# Sheet1.net
KiCad netlist of a schematic drawn in Altium Designer
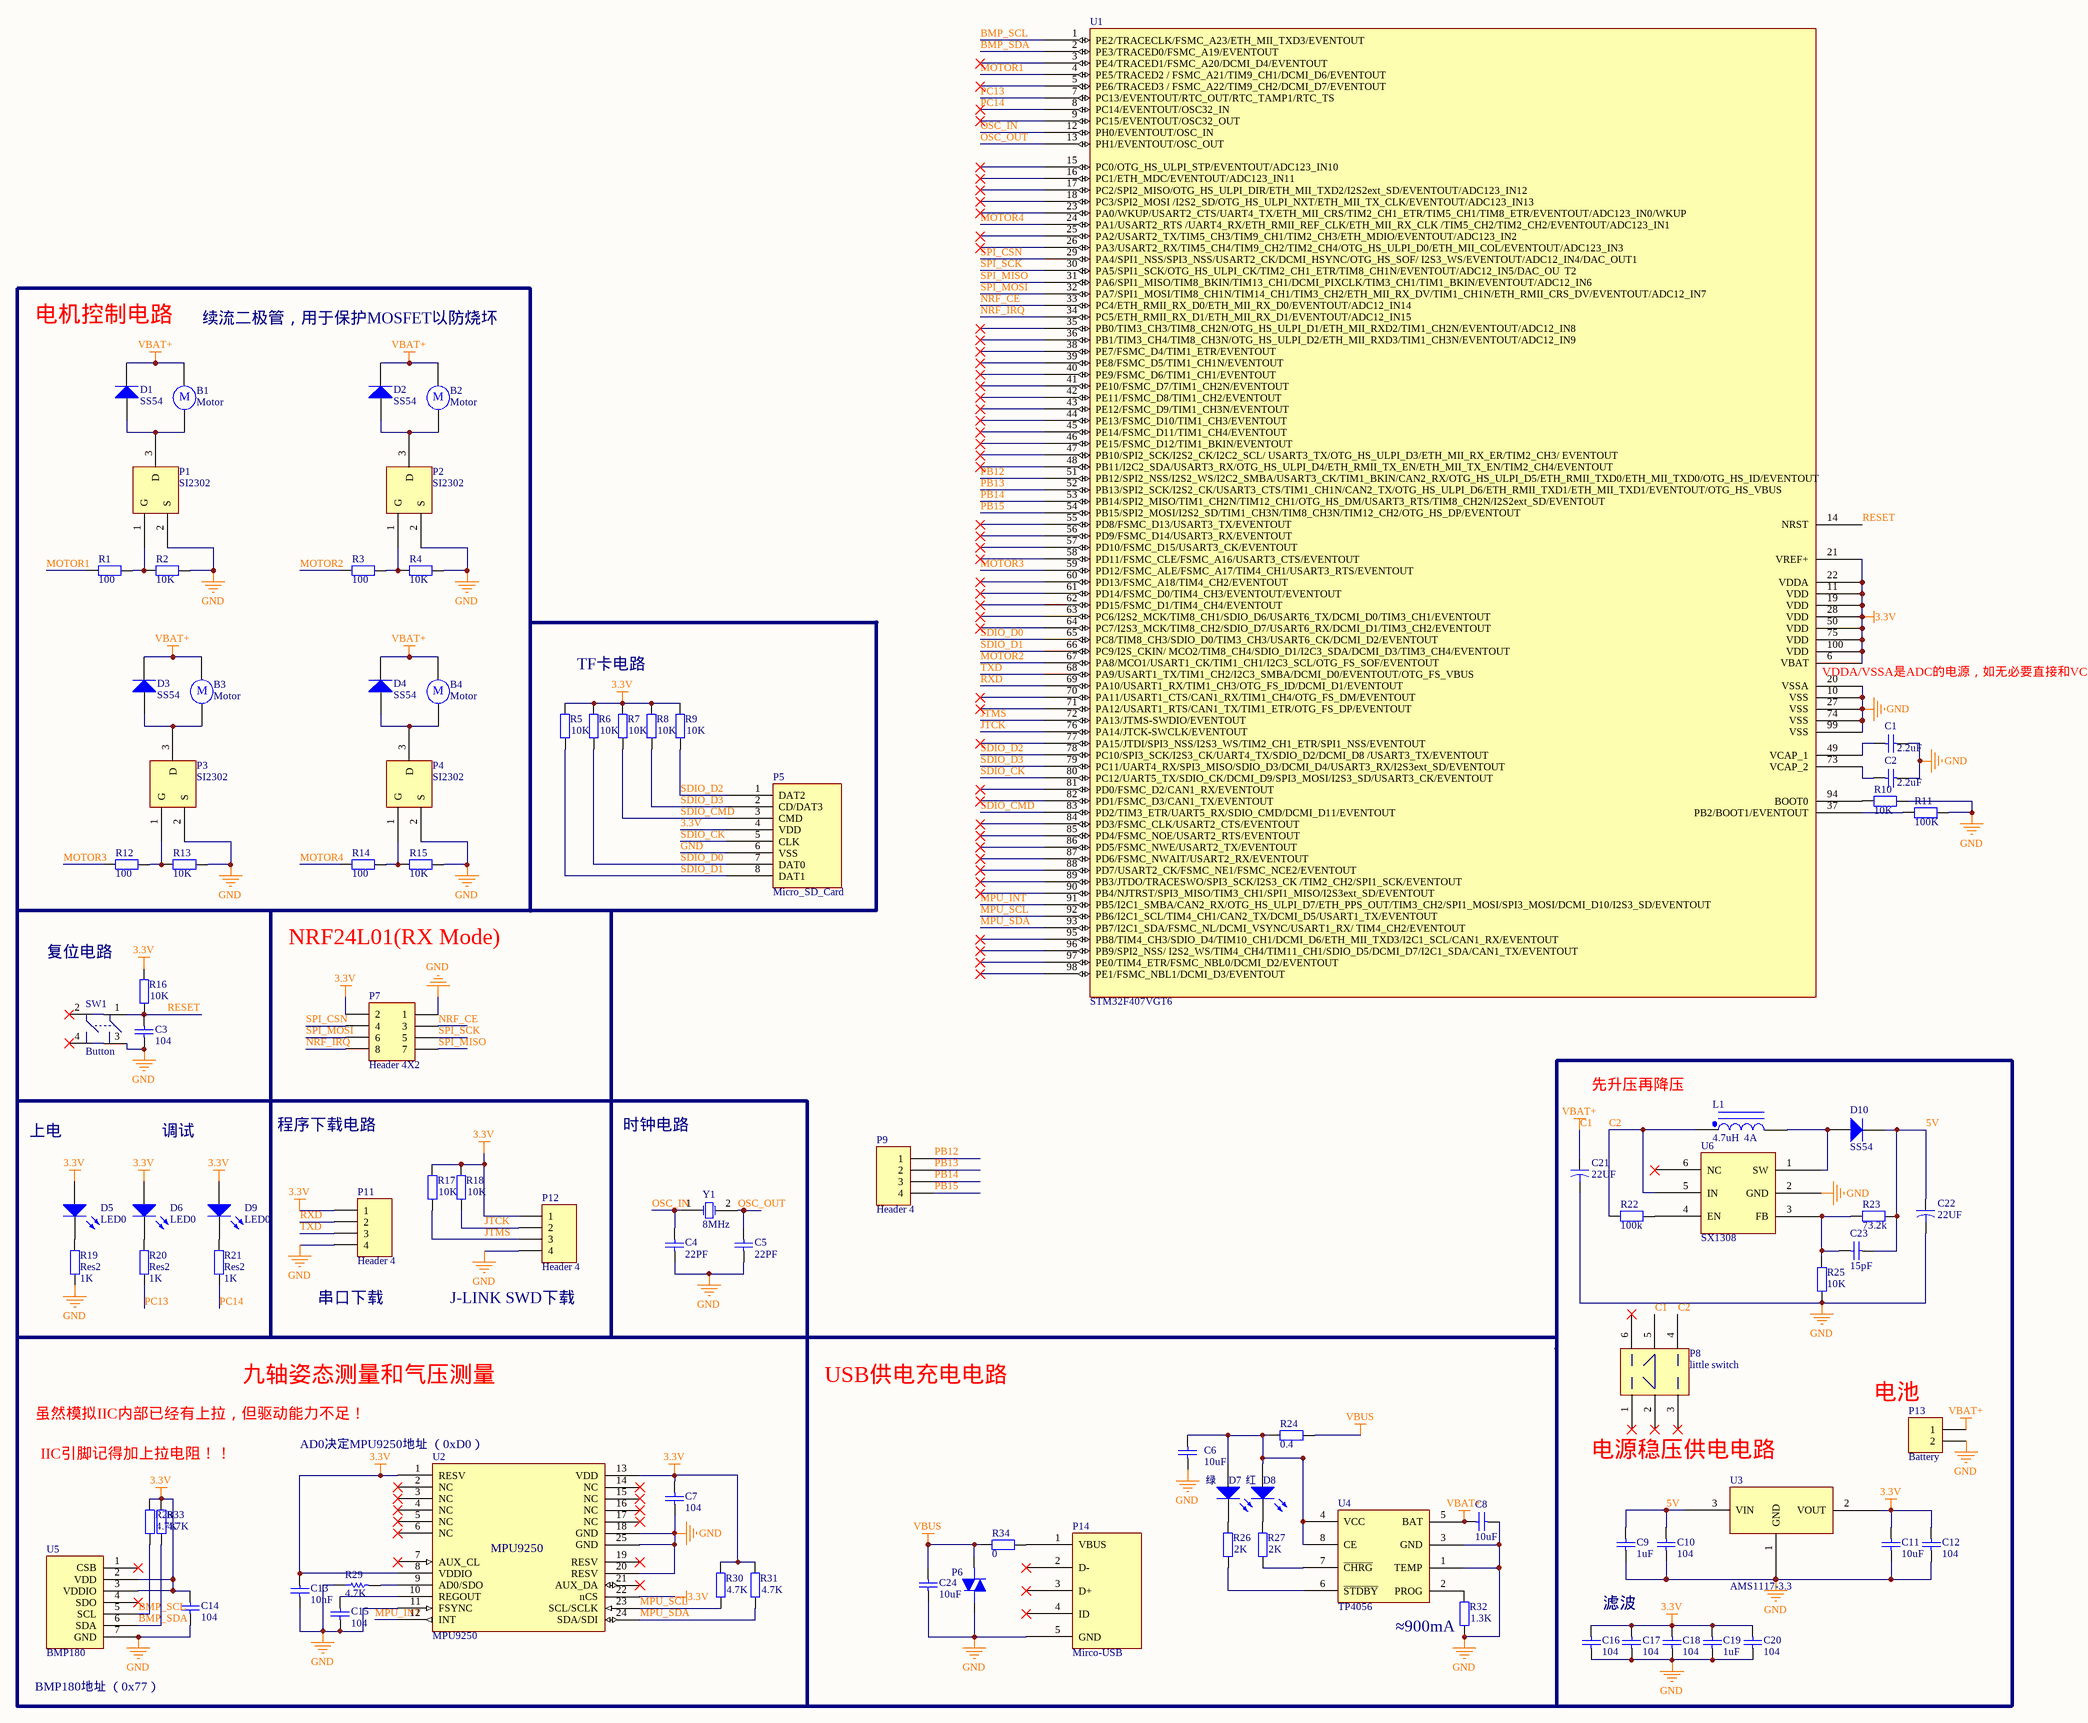
[diagram p0: Sheet1.SchDoc]

(export (version "E")
  (design (tool "Eeschema 10.0.6"))
  (components
    (comp (ref "B1")
      (value "Motor")
      (footprint "BAT-2")
      (description "Motor, General Kind")
      (fields (field (name "PUBLISHER") "Altium Limited"))
      (libsource (lib "Miscellaneous Devices") (part "Motor"))
    )
    (comp (ref "B2")
      (value "Motor")
      (footprint "BAT-2")
      (description "Motor, General Kind")
      (fields (field (name "PUBLISHER") "Altium Limited"))
      (libsource (lib "Miscellaneous Devices") (part "Motor"))
    )
    (comp (ref "B3")
      (value "Motor")
      (footprint "BAT-2")
      (description "Motor, General Kind")
      (fields (field (name "PUBLISHER") "Altium Limited"))
      (libsource (lib "Miscellaneous Devices") (part "Motor"))
    )
    (comp (ref "B4")
      (value "Motor")
      (footprint "BAT-2")
      (description "Motor, General Kind")
      (fields (field (name "PUBLISHER") "Altium Limited"))
      (libsource (lib "Miscellaneous Devices") (part "Motor"))
    )
    (comp (ref "C1")
      (value "2.2uF")
      (footprint "0603")
      (description "Capacitor")
      (fields (field (name "Comment") "Cap") (field (name "PUBLISHER") "Altium Limited"))
      (libsource (lib "Miscellaneous Devices") (part "Cap"))
    )
    (comp (ref "C2")
      (value "2.2uF")
      (footprint "0603")
      (description "Capacitor")
      (fields (field (name "Comment") "Cap") (field (name "PUBLISHER") "Altium Limited"))
      (libsource (lib "Miscellaneous Devices") (part "Cap"))
    )
    (comp (ref "C3")
      (value "104")
      (footprint "0603")
      (description "Capacitor")
      (fields (field (name "Comment") "Cap") (field (name "PUBLISHER") "Altium Limited"))
      (libsource (lib "Miscellaneous Devices") (part "Cap"))
    )
    (comp (ref "C4")
      (value "22PF")
      (footprint "0603")
      (description "Capacitor")
      (fields (field (name "Comment") "Cap") (field (name "PUBLISHER") "Altium Limited"))
      (libsource (lib "Miscellaneous Devices") (part "Cap"))
    )
    (comp (ref "C5")
      (value "22PF")
      (footprint "0603")
      (description "Capacitor")
      (fields (field (name "Comment") "Cap") (field (name "PUBLISHER") "Altium Limited"))
      (libsource (lib "Miscellaneous Devices") (part "Cap"))
    )
    (comp (ref "C6")
      (value "10uF")
      (footprint "0603")
      (description "Capacitor")
      (fields (field (name "Comment") "Cap") (field (name "PUBLISHER") "Altium Limited"))
      (libsource (lib "Miscellaneous Devices") (part "Cap"))
    )
    (comp (ref "C7")
      (value "104")
      (footprint "0603")
      (description "Capacitor")
      (fields (field (name "Comment") "Cap") (field (name "PUBLISHER") "Altium Limited"))
      (libsource (lib "Miscellaneous Devices") (part "Cap"))
    )
    (comp (ref "C8")
      (value "10uF")
      (footprint "0603")
      (description "Capacitor")
      (fields (field (name "Comment") "Cap") (field (name "PUBLISHER") "Altium Limited"))
      (libsource (lib "Miscellaneous Devices") (part "Cap"))
    )
    (comp (ref "C9")
      (value "1uF")
      (footprint "0603")
      (description "Capacitor")
      (fields (field (name "Comment") "Cap") (field (name "PUBLISHER") "Altium Limited"))
      (libsource (lib "Miscellaneous Devices") (part "Cap"))
    )
    (comp (ref "C10")
      (value "104")
      (footprint "0603")
      (description "Capacitor")
      (fields (field (name "Comment") "Cap") (field (name "PUBLISHER") "Altium Limited"))
      (libsource (lib "Miscellaneous Devices") (part "Cap"))
    )
    (comp (ref "C11")
      (value "10uF")
      (footprint "0603")
      (description "Capacitor")
      (fields (field (name "Comment") "Cap") (field (name "PUBLISHER") "Altium Limited"))
      (libsource (lib "Miscellaneous Devices") (part "Cap"))
    )
    (comp (ref "C12")
      (value "104")
      (footprint "0603")
      (description "Capacitor")
      (fields (field (name "Comment") "Cap") (field (name "PUBLISHER") "Altium Limited"))
      (libsource (lib "Miscellaneous Devices") (part "Cap"))
    )
    (comp (ref "C13")
      (value "10nF")
      (footprint "0603")
      (description "Capacitor")
      (fields (field (name "Comment") "Cap") (field (name "PUBLISHER") "Altium Limited"))
      (libsource (lib "Miscellaneous Devices") (part "Cap"))
    )
    (comp (ref "C14")
      (value "104")
      (footprint "0603")
      (description "Capacitor")
      (fields (field (name "Comment") "Cap") (field (name "PUBLISHER") "Altium Limited"))
      (libsource (lib "Miscellaneous Devices") (part "Cap"))
    )
    (comp (ref "C15")
      (value "104")
      (footprint "0603")
      (description "Capacitor")
      (fields (field (name "Comment") "Cap") (field (name "PUBLISHER") "Altium Limited"))
      (libsource (lib "Miscellaneous Devices") (part "Cap"))
    )
    (comp (ref "C16")
      (value "104")
      (footprint "0603")
      (description "Capacitor")
      (fields (field (name "Comment") "Cap") (field (name "PUBLISHER") "Altium Limited"))
      (libsource (lib "Miscellaneous Devices") (part "Cap"))
    )
    (comp (ref "C17")
      (value "104")
      (footprint "0603")
      (description "Capacitor")
      (fields (field (name "Comment") "Cap") (field (name "PUBLISHER") "Altium Limited"))
      (libsource (lib "Miscellaneous Devices") (part "Cap"))
    )
    (comp (ref "C18")
      (value "104")
      (footprint "0603")
      (description "Capacitor")
      (fields (field (name "Comment") "Cap") (field (name "PUBLISHER") "Altium Limited"))
      (libsource (lib "Miscellaneous Devices") (part "Cap"))
    )
    (comp (ref "C19")
      (value "1uF")
      (footprint "0603")
      (description "Capacitor")
      (fields (field (name "Comment") "Cap") (field (name "PUBLISHER") "Altium Limited"))
      (libsource (lib "Miscellaneous Devices") (part "Cap"))
    )
    (comp (ref "C20")
      (value "104")
      (footprint "0603")
      (description "Capacitor")
      (fields (field (name "Comment") "Cap") (field (name "PUBLISHER") "Altium Limited"))
      (libsource (lib "Miscellaneous Devices") (part "Cap"))
    )
    (comp (ref "C21")
      (value "22UF")
      (footprint "0603")
      (description "Capacitor")
      (fields (field (name "Comment") "Cap2") (field (name "PUBLISHER") "Altium Limited"))
      (libsource (lib "Miscellaneous Devices") (part "Cap2"))
    )
    (comp (ref "C22")
      (value "22UF")
      (footprint "0603")
      (description "Capacitor")
      (fields (field (name "Comment") "Cap2") (field (name "PUBLISHER") "Altium Limited"))
      (libsource (lib "Miscellaneous Devices") (part "Cap2"))
    )
    (comp (ref "C23")
      (value "15pF")
      (footprint "0603")
      (description "Capacitor")
      (fields (field (name "Comment") "Cap") (field (name "PUBLISHER") "Altium Limited"))
      (libsource (lib "Miscellaneous Devices") (part "Cap"))
    )
    (comp (ref "C24")
      (value "10uF")
      (footprint "0603")
      (description "Capacitor")
      (fields (field (name "Comment") "Cap") (field (name "PUBLISHER") "Altium Limited"))
      (libsource (lib "Miscellaneous Devices") (part "Cap"))
    )
    (comp (ref "D1")
      (value "SS54")
      (footprint "DO-214AA/SMB")
      (description "Default Diode")
      (fields (field (name "PUBLISHER") "Altium Limited"))
      (libsource (lib "Miscellaneous Devices") (part "Diode"))
    )
    (comp (ref "D2")
      (value "SS54")
      (footprint "DO-214AA/SMB")
      (description "Default Diode")
      (fields (field (name "PUBLISHER") "Altium Limited"))
      (libsource (lib "Miscellaneous Devices") (part "Diode"))
    )
    (comp (ref "D3")
      (value "SS54")
      (footprint "DO-214AA/SMB")
      (description "Default Diode")
      (fields (field (name "PUBLISHER") "Altium Limited"))
      (libsource (lib "Miscellaneous Devices") (part "Diode"))
    )
    (comp (ref "D4")
      (value "SS54")
      (footprint "DO-214AA/SMB")
      (description "Default Diode")
      (fields (field (name "PUBLISHER") "Altium Limited"))
      (libsource (lib "Miscellaneous Devices") (part "Diode"))
    )
    (comp (ref "D5")
      (value "LED0")
      (footprint "0603-LED")
      (description "Typical INFRARED GaAs LED")
      (fields (field (name "PUBLISHER") "Altium Limited"))
      (libsource (lib "Miscellaneous Devices") (part "LED0"))
    )
    (comp (ref "D6")
      (value "LED0")
      (footprint "0603-LED")
      (description "Typical INFRARED GaAs LED")
      (fields (field (name "PUBLISHER") "Altium Limited"))
      (libsource (lib "Miscellaneous Devices") (part "LED0"))
    )
    (comp (ref "D7")
      (value "绿")
      (footprint "0603-LED")
      (description "Typical INFRARED GaAs LED")
      (fields (field (name "PUBLISHER") "Altium Limited"))
      (libsource (lib "Miscellaneous Devices") (part "LED0"))
    )
    (comp (ref "D8")
      (value "红")
      (footprint "0603-LED")
      (description "Typical INFRARED GaAs LED")
      (fields (field (name "PUBLISHER") "Altium Limited"))
      (libsource (lib "Miscellaneous Devices") (part "LED0"))
    )
    (comp (ref "D9")
      (value "LED0")
      (footprint "0603-LED")
      (description "Typical INFRARED GaAs LED")
      (fields (field (name "PUBLISHER") "Altium Limited"))
      (libsource (lib "Miscellaneous Devices") (part "LED0"))
    )
    (comp (ref "D10")
      (value "SS54")
      (footprint "DO-214AA/SMB")
      (description "Default Diode")
      (fields (field (name "PUBLISHER") "Altium Limited"))
      (libsource (lib "Miscellaneous Devices") (part "Diode"))
    )
    (comp (ref "L1")
      (value "4.7uH  4A")
      (footprint "0603")
      (description "Magnetic-Core Inductor with Winding Polarity Marking")
      (fields (field (name "Comment") "Inductor Iron Dot") (field (name "PUBLISHER") "Altium Limited"))
      (libsource (lib "Miscellaneous Devices") (part "Inductor Iron Dot"))
    )
    (comp (ref "P1")
      (value "SI2302")
      (footprint "SOT-23")
      (description "MOSFET")
      (libsource (lib "Schlib1") (part "SI2302"))
    )
    (comp (ref "P2")
      (value "SI2302")
      (footprint "SOT-23")
      (description "MOSFET")
      (libsource (lib "Schlib1") (part "SI2302"))
    )
    (comp (ref "P3")
      (value "SI2302")
      (footprint "SOT-23")
      (description "MOSFET")
      (libsource (lib "Schlib1") (part "SI2302"))
    )
    (comp (ref "P4")
      (value "SI2302")
      (footprint "SOT-23")
      (description "MOSFET")
      (libsource (lib "Schlib1") (part "SI2302"))
    )
    (comp (ref "P5")
      (value "Micro_SD_Card")
      (footprint "Micro SD Card")
      (libsource (lib "Schlib1") (part "Micro_SD_Card"))
    )
    (comp (ref "P6") (value "PESD5V0ST1BA") (footprint "0603") (libsource (lib "SuZe") (part "esd9b5.0st5g")))
    (comp (ref "P7")
      (value "Header 4X2")
      (footprint "HDR2X4")
      (description "Header, 4-Pin, Dual row")
      (fields (field (name "PUBLISHER") "Altium Limited"))
      (libsource (lib "Miscellaneous Connectors") (part "Header 4X2"))
    )
    (comp (ref "P8")
      (value "little switch")
      (footprint "little switch")
      (libsource (lib "Schlib1") (part "little switch"))
    )
    (comp (ref "P9")
      (value "Header 4")
      (footprint "HDR1X4")
      (description "Header, 4-Pin")
      (fields (field (name "PUBLISHER") "Altium Limited"))
      (libsource (lib "") (part "Header 4_1"))
    )
    (comp (ref "P11")
      (value "Header 4")
      (footprint "HDR1X4")
      (description "Header, 4-Pin")
      (fields (field (name "PUBLISHER") "Altium Limited"))
      (libsource (lib "Miscellaneous Connectors") (part "Header 4"))
    )
    (comp (ref "P12")
      (value "Header 4")
      (footprint "HDR1X4")
      (description "Header, 4-Pin")
      (fields (field (name "PUBLISHER") "Altium Limited"))
      (libsource (lib "Miscellaneous Connectors") (part "Header 4"))
    )
    (comp (ref "P13")
      (value "Battery")
      (footprint "HDR1X2")
      (description "Header, 2-Pin")
      (fields (field (name "PUBLISHER") "Altium Limited"))
      (libsource (lib "Miscellaneous Connectors") (part "Header 2"))
    )
    (comp (ref "P14")
      (value "Mirco-USB")
      (footprint "microUSB2")
      (description "USB")
      (libsource (lib "Schlib1") (part "Mirco-USB"))
    )
    (comp (ref "R1")
      (value "100")
      (footprint "0603")
      (description "Resistor")
      (fields (field (name "Comment") "Res2") (field (name "PUBLISHER") "Altium Limited"))
      (libsource (lib "") (part "Res2_1"))
    )
    (comp (ref "R2")
      (value "10K")
      (footprint "0603")
      (description "Resistor")
      (fields (field (name "Comment") "Res2") (field (name "PUBLISHER") "Altium Limited"))
      (libsource (lib "") (part "Res2_1"))
    )
    (comp (ref "R3")
      (value "100")
      (footprint "0603")
      (description "Resistor")
      (fields (field (name "Comment") "Res2") (field (name "PUBLISHER") "Altium Limited"))
      (libsource (lib "") (part "Res2_1"))
    )
    (comp (ref "R4")
      (value "10K")
      (footprint "0603")
      (description "Resistor")
      (fields (field (name "Comment") "Res2") (field (name "PUBLISHER") "Altium Limited"))
      (libsource (lib "") (part "Res2_1"))
    )
    (comp (ref "R5")
      (value "10K")
      (footprint "0603")
      (description "Resistor")
      (fields (field (name "Comment") "Res2") (field (name "PUBLISHER") "Altium Limited"))
      (libsource (lib "Miscellaneous Devices") (part "Res2"))
    )
    (comp (ref "R6")
      (value "10K")
      (footprint "0603")
      (description "Resistor")
      (fields (field (name "Comment") "Res2") (field (name "PUBLISHER") "Altium Limited"))
      (libsource (lib "Miscellaneous Devices") (part "Res2"))
    )
    (comp (ref "R7")
      (value "10K")
      (footprint "0603")
      (description "Resistor")
      (fields (field (name "Comment") "Res2") (field (name "PUBLISHER") "Altium Limited"))
      (libsource (lib "Miscellaneous Devices") (part "Res2"))
    )
    (comp (ref "R8")
      (value "10K")
      (footprint "0603")
      (description "Resistor")
      (fields (field (name "Comment") "Res2") (field (name "PUBLISHER") "Altium Limited"))
      (libsource (lib "Miscellaneous Devices") (part "Res2"))
    )
    (comp (ref "R9")
      (value "10K")
      (footprint "0603")
      (description "Resistor")
      (fields (field (name "Comment") "Res2") (field (name "PUBLISHER") "Altium Limited"))
      (libsource (lib "Miscellaneous Devices") (part "Res2"))
    )
    (comp (ref "R10")
      (value "10K")
      (footprint "0603")
      (description "Resistor")
      (fields (field (name "Comment") "Res2") (field (name "PUBLISHER") "Altium Limited"))
      (libsource (lib "") (part "Res2_1"))
    )
    (comp (ref "R11")
      (value "100K")
      (footprint "0603")
      (description "Resistor")
      (fields (field (name "Comment") "Res2") (field (name "PUBLISHER") "Altium Limited"))
      (libsource (lib "") (part "Res2_1"))
    )
    (comp (ref "R12")
      (value "100")
      (footprint "0603")
      (description "Resistor")
      (fields (field (name "Comment") "Res2") (field (name "PUBLISHER") "Altium Limited"))
      (libsource (lib "") (part "Res2_1"))
    )
    (comp (ref "R13")
      (value "10K")
      (footprint "0603")
      (description "Resistor")
      (fields (field (name "Comment") "Res2") (field (name "PUBLISHER") "Altium Limited"))
      (libsource (lib "") (part "Res2_1"))
    )
    (comp (ref "R14")
      (value "100")
      (footprint "0603")
      (description "Resistor")
      (fields (field (name "Comment") "Res2") (field (name "PUBLISHER") "Altium Limited"))
      (libsource (lib "") (part "Res2_1"))
    )
    (comp (ref "R15")
      (value "10K")
      (footprint "0603")
      (description "Resistor")
      (fields (field (name "Comment") "Res2") (field (name "PUBLISHER") "Altium Limited"))
      (libsource (lib "") (part "Res2_1"))
    )
    (comp (ref "R16")
      (value "10K")
      (footprint "0603")
      (description "Resistor")
      (fields (field (name "Comment") "Res2") (field (name "PUBLISHER") "Altium Limited"))
      (libsource (lib "Miscellaneous Devices") (part "Res2"))
    )
    (comp (ref "R17")
      (value "10K")
      (footprint "0603")
      (description "Resistor")
      (fields (field (name "Comment") "Res2") (field (name "PUBLISHER") "Altium Limited"))
      (libsource (lib "Miscellaneous Devices") (part "Res2"))
    )
    (comp (ref "R18")
      (value "10K")
      (footprint "0603")
      (description "Resistor")
      (fields (field (name "Comment") "Res2") (field (name "PUBLISHER") "Altium Limited"))
      (libsource (lib "Miscellaneous Devices") (part "Res2"))
    )
    (comp (ref "R19")
      (value "Res2")
      (footprint "0603")
      (description "Resistor")
      (fields (field (name "ALTIUM_VALUE") "1K") (field (name "PUBLISHER") "Altium Limited"))
      (libsource (lib "Miscellaneous Devices") (part "Res2"))
    )
    (comp (ref "R20")
      (value "Res2")
      (footprint "0603")
      (description "Resistor")
      (fields (field (name "ALTIUM_VALUE") "1K") (field (name "PUBLISHER") "Altium Limited"))
      (libsource (lib "Miscellaneous Devices") (part "Res2"))
    )
    (comp (ref "R21")
      (value "Res2")
      (footprint "0603")
      (description "Resistor")
      (fields (field (name "ALTIUM_VALUE") "1K") (field (name "PUBLISHER") "Altium Limited"))
      (libsource (lib "Miscellaneous Devices") (part "Res2"))
    )
    (comp (ref "R22")
      (value "100k")
      (footprint "0603")
      (description "Resistor")
      (fields (field (name "Comment") "Res2") (field (name "PUBLISHER") "Altium Limited"))
      (libsource (lib "") (part "Res2_1"))
    )
    (comp (ref "R23")
      (value "73.2k")
      (footprint "0603")
      (description "Resistor")
      (fields (field (name "Comment") "Res2") (field (name "PUBLISHER") "Altium Limited"))
      (libsource (lib "") (part "Res2_1"))
    )
    (comp (ref "R24")
      (value "0.4")
      (footprint "0603")
      (description "Resistor")
      (fields (field (name "Comment") "Res2") (field (name "PUBLISHER") "Altium Limited"))
      (libsource (lib "") (part "Res2_1"))
    )
    (comp (ref "R25")
      (value "10K")
      (footprint "0603")
      (description "Resistor")
      (fields (field (name "Comment") "Res2") (field (name "PUBLISHER") "Altium Limited"))
      (libsource (lib "Miscellaneous Devices") (part "Res2"))
    )
    (comp (ref "R26")
      (value "2K")
      (footprint "0603")
      (description "Resistor")
      (fields (field (name "Comment") "Res2") (field (name "PUBLISHER") "Altium Limited"))
      (libsource (lib "Miscellaneous Devices") (part "Res2"))
    )
    (comp (ref "R27")
      (value "2K")
      (footprint "0603")
      (description "Resistor")
      (fields (field (name "Comment") "Res2") (field (name "PUBLISHER") "Altium Limited"))
      (libsource (lib "Miscellaneous Devices") (part "Res2"))
    )
    (comp (ref "R28")
      (value "4.7K")
      (footprint "0603")
      (description "Resistor")
      (fields (field (name "Comment") "Res2") (field (name "PUBLISHER") "Altium Limited"))
      (libsource (lib "Miscellaneous Devices") (part "Res2"))
    )
    (comp (ref "R29")
      (value "4.7K")
      (footprint "0603")
      (description "Resistor")
      (fields (field (name "Comment") "Res1") (field (name "PUBLISHER") "Altium Limited"))
      (libsource (lib "Miscellaneous Devices") (part "Res1"))
    )
    (comp (ref "R30")
      (value "4.7K")
      (footprint "0603")
      (description "Resistor")
      (fields (field (name "Comment") "Res2") (field (name "PUBLISHER") "Altium Limited"))
      (libsource (lib "Miscellaneous Devices") (part "Res2"))
    )
    (comp (ref "R31")
      (value "4.7K")
      (footprint "0603")
      (description "Resistor")
      (fields (field (name "Comment") "Res2") (field (name "PUBLISHER") "Altium Limited"))
      (libsource (lib "Miscellaneous Devices") (part "Res2"))
    )
    (comp (ref "R32")
      (value "1.3K")
      (footprint "0603")
      (description "Resistor")
      (fields (field (name "Comment") "Res2") (field (name "PUBLISHER") "Altium Limited"))
      (libsource (lib "Miscellaneous Devices") (part "Res2"))
    )
    (comp (ref "R33")
      (value "4.7K")
      (footprint "0603")
      (description "Resistor")
      (fields (field (name "Comment") "Res2") (field (name "PUBLISHER") "Altium Limited"))
      (libsource (lib "Miscellaneous Devices") (part "Res2"))
    )
    (comp (ref "R34")
      (value "0")
      (footprint "0603")
      (description "Resistor")
      (fields (field (name "Comment") "Res2") (field (name "PUBLISHER") "Altium Limited"))
      (libsource (lib "") (part "Res2_1"))
    )
    (comp (ref "SW1")
      (value "Button")
      (footprint "SMD,5.1x5.1mm - duplicate")
      (libsource (lib "Schlib1") (part "Button"))
    )
    (comp (ref "U1")
      (value "STM32F407VGT6")
      (footprint "LQFP-100")
      (description "ST MCU")
      (libsource (lib "Schlib1") (part "STM32F407VGT6"))
    )
    (comp (ref "U2")
      (value "MPU9250")
      (footprint "QFN24")
      (description "IMU")
      (libsource (lib "Schlib1") (part "MPU9250"))
    )
    (comp (ref "U3")
      (value "AMS1117-3.3")
      (footprint "SOT-223")
      (description "5V->3.3V")
      (libsource (lib "Schlib1") (part "AMS1117-3.3"))
    )
    (comp (ref "U4")
      (value "TP4056")
      (footprint "SOIC-8/SOP-8")
      (description "Battery Charge IC")
      (libsource (lib "Schlib1") (part "TP4056"))
    )
    (comp (ref "U5")
      (value "BMP180")
      (footprint "BMP180")
      (description "atmospheric pressure sensor")
      (libsource (lib "Schlib1") (part "BMP180"))
    )
    (comp (ref "U6") (value "SX1308") (footprint "sot-23-6") (libsource (lib "Schlib1") (part "SX1308")))
    (comp (ref "Y1")
      (value "8MHz")
      (footprint "LC-HC-49S")
      (description "Crystal Oscillator")
      (fields (field (name "PUBLISHER") "Altium Limited"))
      (libsource (lib "Miscellaneous Devices") (part "XTAL"))
    )
  )
  (nets
    (net (code "1") (name "/5V") (class "Default")
      (node (ref "C10") (pin "2") (pinfunction "2_2") (pintype "passive"))
      (node (ref "C22") (pin "1") (pinfunction "1_1") (pintype "passive"))
      (node (ref "C23") (pin "1") (pinfunction "1_1") (pintype "passive"))
      (node (ref "C9") (pin "2") (pinfunction "2_2") (pintype "passive"))
      (node (ref "D10") (pin "2") (pinfunction "K_2") (pintype "passive"))
      (node (ref "R23") (pin "1") (pinfunction "1_1") (pintype "passive"))
      (node (ref "U3") (pin "3") (pinfunction "VIN_3") (pintype "power_in"))
    )
    (net (code "2") (name "/BMP_SCL") (class "Default")
      (node (ref "R28") (pin "1") (pinfunction "1_1") (pintype "passive"))
      (node (ref "U1") (pin "1") (pinfunction "PE2/TRACECLK/FSMC_A23/ETH_MII_TXD3/EVENTOUT_1") (pintype "bidirectional"))
      (node (ref "U5") (pin "5") (pinfunction "SCL_5") (pintype "passive"))
    )
    (net (code "3") (name "/BMP_SDA") (class "Default")
      (node (ref "R33") (pin "1") (pinfunction "1_1") (pintype "passive"))
      (node (ref "U1") (pin "2") (pinfunction "PE3/TRACED0/FSMC_A19/EVENTOUT_2") (pintype "bidirectional"))
      (node (ref "U5") (pin "6") (pinfunction "SDA_6") (pintype "passive"))
    )
    (net (code "4") (name "/C2") (class "Default")
      (node (ref "L1") (pin "1") (pinfunction "1_1") (pintype "passive"))
      (node (ref "P8") (pin "4") (pinfunction "11_4") (pintype "passive"))
      (node (ref "R22") (pin "2") (pinfunction "2_2") (pintype "passive"))
      (node (ref "U6") (pin "5") (pinfunction "IN_5") (pintype "power_in"))
    )
    (net (code "5") (name "/JTCK") (class "Default")
      (node (ref "P12") (pin "2") (pinfunction "2_2") (pintype "passive"))
      (node (ref "R18") (pin "1") (pinfunction "1_1") (pintype "passive"))
      (node (ref "U1") (pin "76") (pinfunction "PA14/JTCK-SWCLK/EVENTOUT_76") (pintype "bidirectional"))
    )
    (net (code "6") (name "/JTMS") (class "Default")
      (node (ref "P12") (pin "3") (pinfunction "3_3") (pintype "passive"))
      (node (ref "R17") (pin "1") (pinfunction "1_1") (pintype "passive"))
      (node (ref "U1") (pin "72") (pinfunction "PA13/JTMS-SWDIO/EVENTOUT_72") (pintype "bidirectional"))
    )
    (net (code "7") (name "/MOTOR1") (class "Default")
      (node (ref "R1") (pin "2") (pinfunction "2_2") (pintype "passive"))
      (node (ref "U1") (pin "4") (pinfunction "PE5/TRACED2_/_FSMC_A21/TIM9_CH1/DCMI_D6/EVENTOUT_4") (pintype "bidirectional"))
    )
    (net (code "8") (name "/MOTOR2") (class "Default")
      (node (ref "R3") (pin "2") (pinfunction "2_2") (pintype "passive"))
      (node (ref "U1") (pin "67") (pinfunction "PA8/MCO1/USART1_CK/TIM1_CH1/I2C3_SCL/OTG_FS_SOF/EVENTOUT_67") (pintype "bidirectional"))
    )
    (net (code "9") (name "/MOTOR3") (class "Default")
      (node (ref "R12") (pin "2") (pinfunction "2_2") (pintype "passive"))
      (node (ref "U1") (pin "59") (pinfunction "PD12/FSMC_ALE/FSMC_A17/TIM4_CH1/USART3_RTS/EVENTOUT_59") (pintype "bidirectional"))
    )
    (net (code "10") (name "/MOTOR4") (class "Default")
      (node (ref "R14") (pin "2") (pinfunction "2_2") (pintype "passive"))
      (node (ref "U1") (pin "24") (pinfunction "PA1/USART2_RTS_/UART4_RX/ETH_RMII_REF_CLK/ETH_MII_RX_CLK_/TIM5_CH2/TIM2_CH2/EVENTOUT/ADC123_IN1_24") (pintype "bidirectional"))
    )
    (net (code "11") (name "/MPU_INT") (class "Default")
      (node (ref "U1") (pin "91") (pinfunction "PB5/I2C1_SMBA/CAN2_RX/OTG_HS_ULPI_D7/ETH_PPS_OUT/TIM3_CH2/SPI1_MOSI/SPI3_MOSI/DCMI_D10/I2S3_SD/EVENTOUT_91") (pintype "bidirectional"))
      (node (ref "U2") (pin "12") (pinfunction "INT_12") (pintype "output"))
    )
    (net (code "12") (name "/MPU_SCL") (class "Default")
      (node (ref "R30") (pin "1") (pinfunction "1_1") (pintype "passive"))
      (node (ref "U1") (pin "92") (pinfunction "PB6/I2C1_SCL/TIM4_CH1/CAN2_TX/DCMI_D5/USART1_TX/EVENTOUT_92") (pintype "bidirectional"))
      (node (ref "U2") (pin "23") (pinfunction "SCL/SCLK_23") (pintype "input"))
    )
    (net (code "13") (name "/MPU_SDA") (class "Default")
      (node (ref "R31") (pin "1") (pinfunction "1_1") (pintype "passive"))
      (node (ref "U1") (pin "93") (pinfunction "PB7/I2C1_SDA/FSMC_NL/DCMI_VSYNC/USART1_RX/_TIM4_CH2/EVENTOUT_93") (pintype "bidirectional"))
      (node (ref "U2") (pin "24") (pinfunction "SDA/SDI_24") (pintype "bidirectional"))
    )
    (net (code "14") (name "/NRF_CE") (class "Default")
      (node (ref "P7") (pin "3") (pinfunction "3_3") (pintype "passive"))
      (node (ref "U1") (pin "33") (pinfunction "PC4/ETH_RMII_RX_D0/ETH_MII_RX_D0/EVENTOUT/ADC12_IN14_33") (pintype "bidirectional"))
    )
    (net (code "15") (name "/NRF_IRQ") (class "Default")
      (node (ref "P7") (pin "8") (pinfunction "8_8") (pintype "passive"))
      (node (ref "U1") (pin "34") (pinfunction "PC5/ETH_RMII_RX_D1/ETH_MII_RX_D1/EVENTOUT/ADC12_IN15_34") (pintype "bidirectional"))
    )
    (net (code "16") (name "/OSC_IN") (class "Default")
      (node (ref "C4") (pin "2") (pinfunction "2_2") (pintype "passive"))
      (node (ref "U1") (pin "12") (pinfunction "PH0/EVENTOUT/OSC_IN_12") (pintype "bidirectional"))
      (node (ref "Y1") (pin "1") (pinfunction "OSC1_1") (pintype "passive"))
    )
    (net (code "17") (name "/OSC_OUT") (class "Default")
      (node (ref "C5") (pin "2") (pinfunction "2_2") (pintype "passive"))
      (node (ref "U1") (pin "13") (pinfunction "PH1/EVENTOUT/OSC_OUT_13") (pintype "bidirectional"))
      (node (ref "Y1") (pin "2") (pinfunction "OSC2_2") (pintype "passive"))
    )
    (net (code "18") (name "/PB12") (class "Default")
      (node (ref "P9") (pin "1") (pinfunction "1_1") (pintype "passive"))
      (node (ref "U1") (pin "51") (pinfunction "PB12/SPI2_NSS/I2S2_WS/I2C2_SMBA/USART3_CK/TIM1_BKIN/CAN2_RX/OTG_HS_ULPI_D5/ETH_RMII_TXD0/ETH_MII_TXD0/OTG_HS_ID/EVENTOUT_51") (pintype "bidirectional"))
    )
    (net (code "19") (name "/PB13") (class "Default")
      (node (ref "P9") (pin "2") (pinfunction "2_2") (pintype "passive"))
      (node (ref "U1") (pin "52") (pinfunction "PB13/SPI2_SCK/I2S2_CK/USART3_CTS/TIM1_CH1N/CAN2_TX/OTG_HS_ULPI_D6/ETH_RMII_TXD1/ETH_MII_TXD1/EVENTOUT/OTG_HS_VBUS_52") (pintype "bidirectional"))
    )
    (net (code "20") (name "/PB14") (class "Default")
      (node (ref "P9") (pin "3") (pinfunction "3_3") (pintype "passive"))
      (node (ref "U1") (pin "53") (pinfunction "PB14/SPI2_MISO/TIM1_CH2N/TIM12_CH1/OTG_HS_DM/USART3_RTS/TIM8_CH2N/I2S2ext_SD/EVENTOUT_53") (pintype "bidirectional"))
    )
    (net (code "21") (name "/PB15") (class "Default")
      (node (ref "P9") (pin "4") (pinfunction "4_4") (pintype "passive"))
      (node (ref "U1") (pin "54") (pinfunction "PB15/SPI2_MOSI/I2S2_SD/TIM1_CH3N/TIM8_CH3N/TIM12_CH2/OTG_HS_DP/EVENTOUT_54") (pintype "bidirectional"))
    )
    (net (code "22") (name "/PC13") (class "Default")
      (node (ref "R20") (pin "1") (pinfunction "1_1") (pintype "passive"))
      (node (ref "U1") (pin "7") (pinfunction "PC13/EVENTOUT/RTC_OUT/RTC_TAMP1/RTC_TS_7") (pintype "bidirectional"))
    )
    (net (code "23") (name "/PC14") (class "Default")
      (node (ref "R21") (pin "1") (pinfunction "1_1") (pintype "passive"))
      (node (ref "U1") (pin "8") (pinfunction "PC14/EVENTOUT/OSC32_IN_8") (pintype "bidirectional"))
    )
    (net (code "24") (name "/RESET") (class "Default")
      (node (ref "C3") (pin "2") (pinfunction "2_2") (pintype "passive"))
      (node (ref "R16") (pin "1") (pinfunction "1_1") (pintype "passive"))
      (node (ref "SW1") (pin "1") (pinfunction "1_1") (pintype "passive"))
      (node (ref "U1") (pin "14") (pinfunction "NRST_14") (pintype "passive"))
    )
    (net (code "25") (name "/RXD") (class "Default")
      (node (ref "P11") (pin "2") (pinfunction "2_2") (pintype "passive"))
      (node (ref "U1") (pin "69") (pinfunction "PA10/USART1_RX/TIM1_CH3/OTG_FS_ID/DCMI_D1/EVENTOUT_69") (pintype "bidirectional"))
    )
    (net (code "26") (name "/SDIO_CK") (class "Default")
      (node (ref "P5") (pin "5") (pinfunction "CLK_5") (pintype "power_in"))
      (node (ref "U1") (pin "80") (pinfunction "PC12/UART5_TX/SDIO_CK/DCMI_D9/SPI3_MOSI/I2S3_SD/USART3_CK/EVENTOUT_80") (pintype "bidirectional"))
    )
    (net (code "27") (name "/SDIO_CMD") (class "Default")
      (node (ref "P5") (pin "3") (pinfunction "CMD_3") (pintype "power_in"))
      (node (ref "R7") (pin "1") (pinfunction "1_1") (pintype "passive"))
      (node (ref "U1") (pin "83") (pinfunction "PD2/TIM3_ETR/UART5_RX/SDIO_CMD/DCMI_D11/EVENTOUT_83") (pintype "bidirectional"))
    )
    (net (code "28") (name "/SDIO_D0") (class "Default")
      (node (ref "P5") (pin "7") (pinfunction "DAT0_7") (pintype "power_in"))
      (node (ref "R6") (pin "1") (pinfunction "1_1") (pintype "passive"))
      (node (ref "U1") (pin "65") (pinfunction "PC8/TIM8_CH3/SDIO_D0/TIM3_CH3/USART6_CK/DCMI_D2/EVENTOUT_65") (pintype "bidirectional"))
    )
    (net (code "29") (name "/SDIO_D1") (class "Default")
      (node (ref "P5") (pin "8") (pinfunction "DAT1_8") (pintype "power_in"))
      (node (ref "R5") (pin "1") (pinfunction "1_1") (pintype "passive"))
      (node (ref "U1") (pin "66") (pinfunction "PC9/I2S_CKIN/_MCO2/TIM8_CH4/SDIO_D1/I2C3_SDA/DCMI_D3/TIM3_CH4/EVENTOUT_66") (pintype "bidirectional"))
    )
    (net (code "30") (name "/SDIO_D2") (class "Default")
      (node (ref "P5") (pin "1") (pinfunction "DAT2_1") (pintype "power_in"))
      (node (ref "R9") (pin "1") (pinfunction "1_1") (pintype "passive"))
      (node (ref "U1") (pin "78") (pinfunction "PC10/SPI3_SCK/I2S3_CK/UART4_TX/SDIO_D2/DCMI_D8_/USART3_TX/EVENTOUT_78") (pintype "bidirectional"))
    )
    (net (code "31") (name "/SDIO_D3") (class "Default")
      (node (ref "P5") (pin "2") (pinfunction "CD/DAT3_2") (pintype "power_in"))
      (node (ref "R8") (pin "1") (pinfunction "1_1") (pintype "passive"))
      (node (ref "U1") (pin "79") (pinfunction "PC11/UART4_RX/SPI3_MISO/SDIO_D3/DCMI_D4/USART3_RX/I2S3ext_SD/EVENTOUT_79") (pintype "bidirectional"))
    )
    (net (code "32") (name "/SPI_CSN") (class "Default")
      (node (ref "P7") (pin "4") (pinfunction "4_4") (pintype "passive"))
      (node (ref "U1") (pin "29") (pinfunction "PA4/SPI1_NSS/SPI3_NSS/USART2_CK/DCMI_HSYNC/OTG_HS_SOF/_I2S3_WS/EVENTOUT/ADC12_IN4/DAC_OUT1_29") (pintype "bidirectional"))
    )
    (net (code "33") (name "/SPI_MISO") (class "Default")
      (node (ref "P7") (pin "7") (pinfunction "7_7") (pintype "passive"))
      (node (ref "U1") (pin "31") (pinfunction "PA6/SPI1_MISO/TIM8_BKIN/TIM13_CH1/DCMI_PIXCLK/TIM3_CH1/TIM1_BKIN/EVENTOUT/ADC12_IN6_31") (pintype "bidirectional"))
    )
    (net (code "34") (name "/SPI_MOSI") (class "Default")
      (node (ref "P7") (pin "6") (pinfunction "6_6") (pintype "passive"))
      (node (ref "U1") (pin "32") (pinfunction "PA7/SPI1_MOSI/TIM8_CH1N/TIM14_CH1/TIM3_CH2/ETH_MII_RX_DV/TIM1_CH1N/ETH_RMII_CRS_DV/EVENTOUT/ADC12_IN7_32") (pintype "bidirectional"))
    )
    (net (code "35") (name "/SPI_SCK") (class "Default")
      (node (ref "P7") (pin "5") (pinfunction "5_5") (pintype "passive"))
      (node (ref "U1") (pin "30") (pinfunction "PA5/SPI1_SCK/OTG_HS_ULPI_CK/TIM2_CH1_ETR/TIM8_CH1N/EVENTOUT/ADC12_IN5/DAC_OU__T2_30") (pintype "bidirectional"))
    )
    (net (code "36") (name "/TXD") (class "Default")
      (node (ref "P11") (pin "3") (pinfunction "3_3") (pintype "passive"))
      (node (ref "U1") (pin "68") (pinfunction "PA9/USART1_TX/TIM1_CH2/I2C3_SMBA/DCMI_D0/EVENTOUT/OTG_FS_VBUS_68") (pintype "bidirectional"))
    )
    (net (code "37") (name "3.3V") (class "Default")
      (node (ref "C11") (pin "2") (pinfunction "2_2") (pintype "passive"))
      (node (ref "C12") (pin "2") (pinfunction "2_2") (pintype "passive"))
      (node (ref "C13") (pin "1") (pinfunction "1_1") (pintype "passive"))
      (node (ref "C14") (pin "1") (pinfunction "1_1") (pintype "passive"))
      (node (ref "C16") (pin "2") (pinfunction "2_2") (pintype "passive"))
      (node (ref "C17") (pin "2") (pinfunction "2_2") (pintype "passive"))
      (node (ref "C18") (pin "2") (pinfunction "2_2") (pintype "passive"))
      (node (ref "C19") (pin "2") (pinfunction "2_2") (pintype "passive"))
      (node (ref "C20") (pin "2") (pinfunction "2_2") (pintype "passive"))
      (node (ref "C7") (pin "1") (pinfunction "1_1") (pintype "passive"))
      (node (ref "D5") (pin "1") (pinfunction "A_1") (pintype "passive"))
      (node (ref "D6") (pin "1") (pinfunction "A_1") (pintype "passive"))
      (node (ref "D9") (pin "1") (pinfunction "A_1") (pintype "passive"))
      (node (ref "P11") (pin "1") (pinfunction "1_1") (pintype "passive"))
      (node (ref "P12") (pin "1") (pinfunction "1_1") (pintype "passive"))
      (node (ref "P5") (pin "4") (pinfunction "VDD_4") (pintype "power_in"))
      (node (ref "P7") (pin "2") (pinfunction "2_2") (pintype "passive"))
      (node (ref "R16") (pin "2") (pinfunction "2_2") (pintype "passive"))
      (node (ref "R17") (pin "2") (pinfunction "2_2") (pintype "passive"))
      (node (ref "R18") (pin "2") (pinfunction "2_2") (pintype "passive"))
      (node (ref "R28") (pin "2") (pinfunction "2_2") (pintype "passive"))
      (node (ref "R30") (pin "2") (pinfunction "2_2") (pintype "passive"))
      (node (ref "R31") (pin "2") (pinfunction "2_2") (pintype "passive"))
      (node (ref "R33") (pin "2") (pinfunction "2_2") (pintype "passive"))
      (node (ref "R5") (pin "2") (pinfunction "2_2") (pintype "passive"))
      (node (ref "R6") (pin "2") (pinfunction "2_2") (pintype "passive"))
      (node (ref "R7") (pin "2") (pinfunction "2_2") (pintype "passive"))
      (node (ref "R8") (pin "2") (pinfunction "2_2") (pintype "passive"))
      (node (ref "R9") (pin "2") (pinfunction "2_2") (pintype "passive"))
      (node (ref "U1") (pin "100") (pinfunction "VDD_100") (pintype "power_in"))
      (node (ref "U1") (pin "11") (pinfunction "VDD_11") (pintype "power_in"))
      (node (ref "U1") (pin "19") (pinfunction "VDD_19") (pintype "power_in"))
      (node (ref "U1") (pin "21") (pinfunction "VREF+_21") (pintype "passive"))
      (node (ref "U1") (pin "22") (pinfunction "VDDA_22") (pintype "power_in"))
      (node (ref "U1") (pin "28") (pinfunction "VDD_28") (pintype "power_in"))
      (node (ref "U1") (pin "50") (pinfunction "VDD_50") (pintype "power_in"))
      (node (ref "U1") (pin "6") (pinfunction "VBAT_6") (pintype "power_in"))
      (node (ref "U1") (pin "75") (pinfunction "VDD_75") (pintype "power_in"))
      (node (ref "U2") (pin "1") (pinfunction "RESV_1") (pintype "passive"))
      (node (ref "U2") (pin "13") (pinfunction "VDD_13") (pintype "passive"))
      (node (ref "U2") (pin "22") (pinfunction "nCS_22") (pintype "passive"))
      (node (ref "U2") (pin "8") (pinfunction "VDDIO_8") (pintype "power_in"))
      (node (ref "U3") (pin "2") (pinfunction "VOUT_2") (pintype "power_in"))
      (node (ref "U5") (pin "2") (pinfunction "VDD_2") (pintype "passive"))
      (node (ref "U5") (pin "3") (pinfunction "VDDIO_3") (pintype "passive"))
    )
    (net (code "38") (name "GND") (class "Default")
      (node (ref "C1") (pin "2") (pinfunction "2_2") (pintype "passive"))
      (node (ref "C10") (pin "1") (pinfunction "1_1") (pintype "passive"))
      (node (ref "C11") (pin "1") (pinfunction "1_1") (pintype "passive"))
      (node (ref "C12") (pin "1") (pinfunction "1_1") (pintype "passive"))
      (node (ref "C13") (pin "2") (pinfunction "2_2") (pintype "passive"))
      (node (ref "C14") (pin "2") (pinfunction "2_2") (pintype "passive"))
      (node (ref "C15") (pin "2") (pinfunction "2_2") (pintype "passive"))
      (node (ref "C16") (pin "1") (pinfunction "1_1") (pintype "passive"))
      (node (ref "C17") (pin "1") (pinfunction "1_1") (pintype "passive"))
      (node (ref "C18") (pin "1") (pinfunction "1_1") (pintype "passive"))
      (node (ref "C19") (pin "1") (pinfunction "1_1") (pintype "passive"))
      (node (ref "C2") (pin "2") (pinfunction "2_2") (pintype "passive"))
      (node (ref "C20") (pin "1") (pinfunction "1_1") (pintype "passive"))
      (node (ref "C21") (pin "2") (pinfunction "2_2") (pintype "passive"))
      (node (ref "C22") (pin "2") (pinfunction "2_2") (pintype "passive"))
      (node (ref "C24") (pin "1") (pinfunction "1_1") (pintype "passive"))
      (node (ref "C3") (pin "1") (pinfunction "1_1") (pintype "passive"))
      (node (ref "C4") (pin "1") (pinfunction "1_1") (pintype "passive"))
      (node (ref "C5") (pin "1") (pinfunction "1_1") (pintype "passive"))
      (node (ref "C6") (pin "1") (pinfunction "1_1") (pintype "passive"))
      (node (ref "C7") (pin "2") (pinfunction "2_2") (pintype "passive"))
      (node (ref "C8") (pin "2") (pinfunction "2_2") (pintype "passive"))
      (node (ref "C9") (pin "1") (pinfunction "1_1") (pintype "passive"))
      (node (ref "P1") (pin "2") (pinfunction "S_2") (pintype "passive"))
      (node (ref "P11") (pin "4") (pinfunction "4_4") (pintype "passive"))
      (node (ref "P12") (pin "4") (pinfunction "4_4") (pintype "passive"))
      (node (ref "P13") (pin "2") (pinfunction "2_2") (pintype "passive"))
      (node (ref "P14") (pin "5") (pinfunction "GND_5") (pintype "passive"))
      (node (ref "P2") (pin "2") (pinfunction "S_2") (pintype "passive"))
      (node (ref "P3") (pin "2") (pinfunction "S_2") (pintype "passive"))
      (node (ref "P4") (pin "2") (pinfunction "S_2") (pintype "passive"))
      (node (ref "P5") (pin "6") (pinfunction "VSS_6") (pintype "power_in"))
      (node (ref "P6") (pin "2") (pinfunction "M2_2") (pintype "passive"))
      (node (ref "P7") (pin "1") (pinfunction "1_1") (pintype "passive"))
      (node (ref "R10") (pin "1") (pinfunction "1_1") (pintype "passive"))
      (node (ref "R11") (pin "1") (pinfunction "1_1") (pintype "passive"))
      (node (ref "R13") (pin "1") (pinfunction "1_1") (pintype "passive"))
      (node (ref "R15") (pin "1") (pinfunction "1_1") (pintype "passive"))
      (node (ref "R19") (pin "1") (pinfunction "1_1") (pintype "passive"))
      (node (ref "R2") (pin "1") (pinfunction "1_1") (pintype "passive"))
      (node (ref "R25") (pin "1") (pinfunction "1_1") (pintype "passive"))
      (node (ref "R29") (pin "1") (pinfunction "1_1") (pintype "passive"))
      (node (ref "R32") (pin "1") (pinfunction "1_1") (pintype "passive"))
      (node (ref "R4") (pin "1") (pinfunction "1_1") (pintype "passive"))
      (node (ref "SW1") (pin "3") (pinfunction "3_3") (pintype "passive"))
      (node (ref "U1") (pin "10") (pinfunction "VSS_10") (pintype "power_in"))
      (node (ref "U1") (pin "20") (pinfunction "VSSA_20") (pintype "power_in"))
      (node (ref "U1") (pin "27") (pinfunction "VSS_27") (pintype "power_in"))
      (node (ref "U1") (pin "74") (pinfunction "VSS_74") (pintype "power_in"))
      (node (ref "U1") (pin "99") (pinfunction "VSS_99") (pintype "power_in"))
      (node (ref "U2") (pin "11") (pinfunction "FSYNC_11") (pintype "input"))
      (node (ref "U2") (pin "18") (pinfunction "GND_18") (pintype "passive"))
      (node (ref "U2") (pin "20") (pinfunction "RESV_20") (pintype "passive"))
      (node (ref "U2") (pin "25") (pinfunction "GND_25") (pintype "passive"))
      (node (ref "U3") (pin "1") (pinfunction "GND_1") (pintype "power_in"))
      (node (ref "U4") (pin "1") (pinfunction "TEMP_1") (pintype "passive"))
      (node (ref "U4") (pin "3") (pinfunction "GND_3") (pintype "passive"))
      (node (ref "U5") (pin "7") (pinfunction "GND_7") (pintype "passive"))
      (node (ref "U6") (pin "2") (pinfunction "GND_2") (pintype "power_in"))
    )
    (net (code "39") (name "Net-(D1-A)") (class "Default")
      (node (ref "B1") (pin "2") (pinfunction "2_2") (pintype "passive"))
      (node (ref "D1") (pin "1") (pinfunction "A_1") (pintype "passive"))
      (node (ref "P1") (pin "3") (pinfunction "D_3") (pintype "passive"))
    )
    (net (code "40") (name "Net-(D2-A)") (class "Default")
      (node (ref "B2") (pin "2") (pinfunction "2_2") (pintype "passive"))
      (node (ref "D2") (pin "1") (pinfunction "A_1") (pintype "passive"))
      (node (ref "P2") (pin "3") (pinfunction "D_3") (pintype "passive"))
    )
    (net (code "41") (name "Net-(D3-A)") (class "Default")
      (node (ref "B3") (pin "2") (pinfunction "2_2") (pintype "passive"))
      (node (ref "D3") (pin "1") (pinfunction "A_1") (pintype "passive"))
      (node (ref "P3") (pin "3") (pinfunction "D_3") (pintype "passive"))
    )
    (net (code "42") (name "Net-(D4-A)") (class "Default")
      (node (ref "B4") (pin "2") (pinfunction "2_2") (pintype "passive"))
      (node (ref "D4") (pin "1") (pinfunction "A_1") (pintype "passive"))
      (node (ref "P4") (pin "3") (pinfunction "D_3") (pintype "passive"))
    )
    (net (code "43") (name "Net-(D5-K)") (class "Default")
      (node (ref "D5") (pin "2") (pinfunction "K_2") (pintype "passive"))
      (node (ref "R19") (pin "2") (pinfunction "2_2") (pintype "passive"))
    )
    (net (code "44") (name "Net-(D6-K)") (class "Default")
      (node (ref "D6") (pin "2") (pinfunction "K_2") (pintype "passive"))
      (node (ref "R20") (pin "2") (pinfunction "2_2") (pintype "passive"))
    )
    (net (code "45") (name "Net-(D7-A)") (class "Default")
      (node (ref "C6") (pin "2") (pinfunction "2_2") (pintype "passive"))
      (node (ref "D7") (pin "1") (pinfunction "A_1") (pintype "passive"))
      (node (ref "D8") (pin "1") (pinfunction "A_1") (pintype "passive"))
      (node (ref "R24") (pin "2") (pinfunction "2_2") (pintype "passive"))
      (node (ref "U4") (pin "4") (pinfunction "VCC_4") (pintype "passive"))
      (node (ref "U4") (pin "8") (pinfunction "CE_8") (pintype "passive"))
    )
    (net (code "46") (name "Net-(D7-K)") (class "Default")
      (node (ref "D7") (pin "2") (pinfunction "K_2") (pintype "passive"))
      (node (ref "R26") (pin "2") (pinfunction "2_2") (pintype "passive"))
    )
    (net (code "47") (name "Net-(D8-K)") (class "Default")
      (node (ref "D8") (pin "2") (pinfunction "K_2") (pintype "passive"))
      (node (ref "R27") (pin "2") (pinfunction "2_2") (pintype "passive"))
    )
    (net (code "48") (name "Net-(D9-K)") (class "Default")
      (node (ref "D9") (pin "2") (pinfunction "K_2") (pintype "passive"))
      (node (ref "R21") (pin "2") (pinfunction "2_2") (pintype "passive"))
    )
    (net (code "49") (name "Net-(D10-A)") (class "Default")
      (node (ref "D10") (pin "1") (pinfunction "A_1") (pintype "passive"))
      (node (ref "L1") (pin "2") (pinfunction "2_2") (pintype "passive"))
      (node (ref "U6") (pin "1") (pinfunction "SW_1") (pintype "passive"))
    )
    (net (code "50") (name "Net-(P1-G)") (class "Default")
      (node (ref "P1") (pin "1") (pinfunction "G_1") (pintype "passive"))
      (node (ref "R1") (pin "1") (pinfunction "1_1") (pintype "passive"))
      (node (ref "R2") (pin "2") (pinfunction "2_2") (pintype "passive"))
    )
    (net (code "51") (name "Net-(P2-G)") (class "Default")
      (node (ref "P2") (pin "1") (pinfunction "G_1") (pintype "passive"))
      (node (ref "R3") (pin "1") (pinfunction "1_1") (pintype "passive"))
      (node (ref "R4") (pin "2") (pinfunction "2_2") (pintype "passive"))
    )
    (net (code "52") (name "Net-(P3-G)") (class "Default")
      (node (ref "P3") (pin "1") (pinfunction "G_1") (pintype "passive"))
      (node (ref "R12") (pin "1") (pinfunction "1_1") (pintype "passive"))
      (node (ref "R13") (pin "2") (pinfunction "2_2") (pintype "passive"))
    )
    (net (code "53") (name "Net-(P4-G)") (class "Default")
      (node (ref "P4") (pin "1") (pinfunction "G_1") (pintype "passive"))
      (node (ref "R14") (pin "1") (pinfunction "1_1") (pintype "passive"))
      (node (ref "R15") (pin "2") (pinfunction "2_2") (pintype "passive"))
    )
    (net (code "54") (name "Net-(P14-VBUS)") (class "Default")
      (node (ref "P14") (pin "1") (pinfunction "VBUS_1") (pintype "power_in"))
      (node (ref "R34") (pin "1") (pinfunction "1_1") (pintype "passive"))
    )
    (net (code "55") (name "Net-(U1-BOOT0)") (class "Default")
      (node (ref "R10") (pin "2") (pinfunction "2_2") (pintype "passive"))
      (node (ref "U1") (pin "94") (pinfunction "BOOT0_94") (pintype "passive"))
    )
    (net (code "56") (name "Net-(U1-PB2{slash}BOOT1{slash}EVENTOUT)") (class "Default")
      (node (ref "R11") (pin "2") (pinfunction "2_2") (pintype "passive"))
      (node (ref "U1") (pin "37") (pinfunction "PB2/BOOT1/EVENTOUT_37") (pintype "passive"))
    )
    (net (code "57") (name "Net-(U1-VCAP_1)") (class "Default")
      (node (ref "C1") (pin "1") (pinfunction "1_1") (pintype "passive"))
      (node (ref "U1") (pin "49") (pinfunction "VCAP_1_49") (pintype "power_in"))
    )
    (net (code "58") (name "Net-(U1-VCAP_2)") (class "Default")
      (node (ref "C2") (pin "1") (pinfunction "1_1") (pintype "passive"))
      (node (ref "U1") (pin "73") (pinfunction "VCAP_2_73") (pintype "power_in"))
    )
    (net (code "59") (name "Net-(U2-AD0{slash}SDO)") (class "Default")
      (node (ref "R29") (pin "2") (pinfunction "2_2") (pintype "passive"))
      (node (ref "U2") (pin "9") (pinfunction "AD0/SDO_9") (pintype "passive"))
    )
    (net (code "60") (name "Net-(U2-REGOUT)") (class "Default")
      (node (ref "C15") (pin "1") (pinfunction "1_1") (pintype "passive"))
      (node (ref "U2") (pin "10") (pinfunction "REGOUT_10") (pintype "passive"))
    )
    (net (code "61") (name "Net-(U4-PROG)") (class "Default")
      (node (ref "R32") (pin "2") (pinfunction "2_2") (pintype "passive"))
      (node (ref "U4") (pin "2") (pinfunction "PROG_2") (pintype "passive"))
    )
    (net (code "62") (name "Net-(U4-~{CHRG})") (class "Default")
      (node (ref "R27") (pin "1") (pinfunction "1_1") (pintype "passive"))
      (node (ref "U4") (pin "7") (pinfunction "~{CHRG}_7") (pintype "passive"))
    )
    (net (code "63") (name "Net-(U4-~{STDBY})") (class "Default")
      (node (ref "R26") (pin "1") (pinfunction "1_1") (pintype "passive"))
      (node (ref "U4") (pin "6") (pinfunction "~{STDBY}_6") (pintype "passive"))
    )
    (net (code "64") (name "Net-(U6-EN)") (class "Default")
      (node (ref "R22") (pin "1") (pinfunction "1_1") (pintype "passive"))
      (node (ref "U6") (pin "4") (pinfunction "EN_4") (pintype "passive"))
    )
    (net (code "65") (name "Net-(U6-FB)") (class "Default")
      (node (ref "C23") (pin "2") (pinfunction "2_2") (pintype "passive"))
      (node (ref "R23") (pin "2") (pinfunction "2_2") (pintype "passive"))
      (node (ref "R25") (pin "2") (pinfunction "2_2") (pintype "passive"))
      (node (ref "U6") (pin "3") (pinfunction "FB_3") (pintype "passive"))
    )
    (net (code "66") (name "VBAT+") (class "Default")
      (node (ref "B1") (pin "1") (pinfunction "1_1") (pintype "passive"))
      (node (ref "B2") (pin "1") (pinfunction "1_1") (pintype "passive"))
      (node (ref "B3") (pin "1") (pinfunction "1_1") (pintype "passive"))
      (node (ref "B4") (pin "1") (pinfunction "1_1") (pintype "passive"))
      (node (ref "C21") (pin "1") (pinfunction "1_1") (pintype "passive"))
      (node (ref "C8") (pin "1") (pinfunction "1_1") (pintype "passive"))
      (node (ref "D1") (pin "2") (pinfunction "K_2") (pintype "passive"))
      (node (ref "D2") (pin "2") (pinfunction "K_2") (pintype "passive"))
      (node (ref "D3") (pin "2") (pinfunction "K_2") (pintype "passive"))
      (node (ref "D4") (pin "2") (pinfunction "K_2") (pintype "passive"))
      (node (ref "P13") (pin "1") (pinfunction "1_1") (pintype "passive"))
      (node (ref "P8") (pin "5") (pinfunction "12_5") (pintype "passive"))
      (node (ref "U4") (pin "5") (pinfunction "BAT_5") (pintype "passive"))
    )
    (net (code "67") (name "VBUS") (class "Default")
      (node (ref "C24") (pin "2") (pinfunction "2_2") (pintype "passive"))
      (node (ref "P6") (pin "1") (pinfunction "M1_1") (pintype "passive"))
      (node (ref "R24") (pin "1") (pinfunction "1_1") (pintype "passive"))
      (node (ref "R34") (pin "2") (pinfunction "2_2") (pintype "passive"))
    )
    (net (code "68") (name "unconnected-(P8-8-Pad1)") (class "Default")
      (node (ref "P8") (pin "1") (pinfunction "8_1") (pintype "passive+no_connect"))
    )
    (net (code "69") (name "unconnected-(P8-9-Pad2)") (class "Default")
      (node (ref "P8") (pin "2") (pinfunction "9_2") (pintype "passive+no_connect"))
    )
    (net (code "70") (name "unconnected-(P8-10-Pad3)") (class "Default")
      (node (ref "P8") (pin "3") (pinfunction "10_3") (pintype "passive+no_connect"))
    )
    (net (code "71") (name "unconnected-(P8-13-Pad6)") (class "Default")
      (node (ref "P8") (pin "6") (pinfunction "13_6") (pintype "passive+no_connect"))
    )
    (net (code "72") (name "unconnected-(P14-D+-Pad3)") (class "Default")
      (node (ref "P14") (pin "3") (pinfunction "D+_3") (pintype "passive+no_connect"))
    )
    (net (code "73") (name "unconnected-(P14-D--Pad2)") (class "Default")
      (node (ref "P14") (pin "2") (pinfunction "D-_2") (pintype "passive+no_connect"))
    )
    (net (code "74") (name "unconnected-(P14-ID-Pad4)") (class "Default")
      (node (ref "P14") (pin "4") (pinfunction "ID_4") (pintype "passive+no_connect"))
    )
    (net (code "75") (name "unconnected-(SW1-Pad2)") (class "Default")
      (node (ref "SW1") (pin "2") (pinfunction "2_2") (pintype "passive+no_connect"))
    )
    (net (code "76") (name "unconnected-(SW1-Pad4)") (class "Default")
      (node (ref "SW1") (pin "4") (pinfunction "4_4") (pintype "passive+no_connect"))
    )
    (net (code "77") (name "unconnected-(U1-PA0{slash}WKUP{slash}USART2_CTS{slash}UART4_TX{slash}ETH_MII_CRS{slash}TIM2_CH1_ETR{slash}TIM5_CH1{slash}TIM8_ETR{slash}EVENTOUT{slash}ADC123_IN0{slash}WKUP-Pad23)") (class "Default")
      (node (ref "U1") (pin "23") (pinfunction "PA0/WKUP/USART2_CTS/UART4_TX/ETH_MII_CRS/TIM2_CH1_ETR/TIM5_CH1/TIM8_ETR/EVENTOUT/ADC123_IN0/WKUP_23") (pintype "bidirectional+no_connect"))
    )
    (net (code "78") (name "unconnected-(U1-PA2{slash}USART2_TX{slash}TIM5_CH3{slash}TIM9_CH1{slash}TIM2_CH3{slash}ETH_MDIO{slash}EVENTOUT{slash}ADC123_IN2-Pad25)") (class "Default")
      (node (ref "U1") (pin "25") (pinfunction "PA2/USART2_TX/TIM5_CH3/TIM9_CH1/TIM2_CH3/ETH_MDIO/EVENTOUT/ADC123_IN2_25") (pintype "bidirectional+no_connect"))
    )
    (net (code "79") (name "unconnected-(U1-PA3{slash}USART2_RX{slash}TIM5_CH4{slash}TIM9_CH2{slash}TIM2_CH4{slash}OTG_HS_ULPI_D0{slash}ETH_MII_COL{slash}EVENTOUT{slash}ADC123_IN3-Pad26)") (class "Default")
      (node (ref "U1") (pin "26") (pinfunction "PA3/USART2_RX/TIM5_CH4/TIM9_CH2/TIM2_CH4/OTG_HS_ULPI_D0/ETH_MII_COL/EVENTOUT/ADC123_IN3_26") (pintype "bidirectional+no_connect"))
    )
    (net (code "80") (name "unconnected-(U1-PA11{slash}USART1_CTS{slash}CAN1_RX{slash}TIM1_CH4{slash}OTG_FS_DM{slash}EVENTOUT-Pad70)") (class "Default")
      (node (ref "U1") (pin "70") (pinfunction "PA11/USART1_CTS/CAN1_RX/TIM1_CH4/OTG_FS_DM/EVENTOUT_70") (pintype "bidirectional+no_connect"))
    )
    (net (code "81") (name "unconnected-(U1-PA12{slash}USART1_RTS{slash}CAN1_TX{slash}TIM1_ETR{slash}OTG_FS_DP{slash}EVENTOUT-Pad71)") (class "Default")
      (node (ref "U1") (pin "71") (pinfunction "PA12/USART1_RTS/CAN1_TX/TIM1_ETR/OTG_FS_DP/EVENTOUT_71") (pintype "bidirectional+no_connect"))
    )
    (net (code "82") (name "unconnected-(U1-PA15{slash}JTDI{slash}SPI3_NSS{slash}I2S3_WS{slash}TIM2_CH1_ETR{slash}SPI1_NSS{slash}EVENTOUT-Pad77)") (class "Default")
      (node (ref "U1") (pin "77") (pinfunction "PA15/JTDI/SPI3_NSS/I2S3_WS/TIM2_CH1_ETR/SPI1_NSS/EVENTOUT_77") (pintype "bidirectional+no_connect"))
    )
    (net (code "83") (name "unconnected-(U1-PB0{slash}TIM3_CH3{slash}TIM8_CH2N{slash}OTG_HS_ULPI_D1{slash}ETH_MII_RXD2{slash}TIM1_CH2N{slash}EVENTOUT{slash}ADC12_IN8-Pad35)") (class "Default")
      (node (ref "U1") (pin "35") (pinfunction "PB0/TIM3_CH3/TIM8_CH2N/OTG_HS_ULPI_D1/ETH_MII_RXD2/TIM1_CH2N/EVENTOUT/ADC12_IN8_35") (pintype "bidirectional+no_connect"))
    )
    (net (code "84") (name "unconnected-(U1-PB1{slash}TIM3_CH4{slash}TIM8_CH3N{slash}OTG_HS_ULPI_D2{slash}ETH_MII_RXD3{slash}TIM1_CH3N{slash}EVENTOUT{slash}ADC12_IN9-Pad36)") (class "Default")
      (node (ref "U1") (pin "36") (pinfunction "PB1/TIM3_CH4/TIM8_CH3N/OTG_HS_ULPI_D2/ETH_MII_RXD3/TIM1_CH3N/EVENTOUT/ADC12_IN9_36") (pintype "bidirectional+no_connect"))
    )
    (net (code "85") (name "unconnected-(U1-PB3{slash}JTDO{slash}TRACESWO{slash}SPI3_SCK{slash}I2S3_CK_{slash}TIM2_CH2{slash}SPI1_SCK{slash}EVENTOUT-Pad89)") (class "Default")
      (node (ref "U1") (pin "89") (pinfunction "PB3/JTDO/TRACESWO/SPI3_SCK/I2S3_CK_/TIM2_CH2/SPI1_SCK/EVENTOUT_89") (pintype "bidirectional+no_connect"))
    )
    (net (code "86") (name "unconnected-(U1-PB4{slash}NJTRST{slash}SPI3_MISO{slash}TIM3_CH1{slash}SPI1_MISO{slash}I2S3ext_SD{slash}EVENTOUT-Pad90)") (class "Default")
      (node (ref "U1") (pin "90") (pinfunction "PB4/NJTRST/SPI3_MISO/TIM3_CH1/SPI1_MISO/I2S3ext_SD/EVENTOUT_90") (pintype "bidirectional+no_connect"))
    )
    (net (code "87") (name "unconnected-(U1-PB8{slash}TIM4_CH3{slash}SDIO_D4{slash}TIM10_CH1{slash}DCMI_D6{slash}ETH_MII_TXD3{slash}I2C1_SCL{slash}CAN1_RX{slash}EVENTOUT-Pad95)") (class "Default")
      (node (ref "U1") (pin "95") (pinfunction "PB8/TIM4_CH3/SDIO_D4/TIM10_CH1/DCMI_D6/ETH_MII_TXD3/I2C1_SCL/CAN1_RX/EVENTOUT_95") (pintype "bidirectional+no_connect"))
    )
    (net (code "88") (name "unconnected-(U1-PB9{slash}SPI2_NSS{slash}_I2S2_WS{slash}TIM4_CH4{slash}TIM11_CH1{slash}SDIO_D5{slash}DCMI_D7{slash}I2C1_SDA{slash}CAN1_TX{slash}EVENTOUT-Pad96)") (class "Default")
      (node (ref "U1") (pin "96") (pinfunction "PB9/SPI2_NSS/_I2S2_WS/TIM4_CH4/TIM11_CH1/SDIO_D5/DCMI_D7/I2C1_SDA/CAN1_TX/EVENTOUT_96") (pintype "bidirectional+no_connect"))
    )
    (net (code "89") (name "unconnected-(U1-PB10{slash}SPI2_SCK{slash}I2S2_CK{slash}I2C2_SCL{slash}_USART3_TX{slash}OTG_HS_ULPI_D3{slash}ETH_MII_RX_ER{slash}TIM2_CH3{slash}_EVENTOUT-Pad47)") (class "Default")
      (node (ref "U1") (pin "47") (pinfunction "PB10/SPI2_SCK/I2S2_CK/I2C2_SCL/_USART3_TX/OTG_HS_ULPI_D3/ETH_MII_RX_ER/TIM2_CH3/_EVENTOUT_47") (pintype "bidirectional+no_connect"))
    )
    (net (code "90") (name "unconnected-(U1-PB11{slash}I2C2_SDA{slash}USART3_RX{slash}OTG_HS_ULPI_D4{slash}ETH_RMII_TX_EN{slash}ETH_MII_TX_EN{slash}TIM2_CH4{slash}EVENTOUT-Pad48)") (class "Default")
      (node (ref "U1") (pin "48") (pinfunction "PB11/I2C2_SDA/USART3_RX/OTG_HS_ULPI_D4/ETH_RMII_TX_EN/ETH_MII_TX_EN/TIM2_CH4/EVENTOUT_48") (pintype "bidirectional+no_connect"))
    )
    (net (code "91") (name "unconnected-(U1-PC0{slash}OTG_HS_ULPI_STP{slash}EVENTOUT{slash}ADC123_IN10-Pad15)") (class "Default")
      (node (ref "U1") (pin "15") (pinfunction "PC0/OTG_HS_ULPI_STP/EVENTOUT/ADC123_IN10_15") (pintype "bidirectional+no_connect"))
    )
    (net (code "92") (name "unconnected-(U1-PC1{slash}ETH_MDC{slash}EVENTOUT{slash}ADC123_IN11-Pad16)") (class "Default")
      (node (ref "U1") (pin "16") (pinfunction "PC1/ETH_MDC/EVENTOUT/ADC123_IN11_16") (pintype "bidirectional+no_connect"))
    )
    (net (code "93") (name "unconnected-(U1-PC2{slash}SPI2_MISO{slash}OTG_HS_ULPI_DIR{slash}ETH_MII_TXD2{slash}I2S2ext_SD{slash}EVENTOUT{slash}ADC123_IN12-Pad17)") (class "Default")
      (node (ref "U1") (pin "17") (pinfunction "PC2/SPI2_MISO/OTG_HS_ULPI_DIR/ETH_MII_TXD2/I2S2ext_SD/EVENTOUT/ADC123_IN12_17") (pintype "bidirectional+no_connect"))
    )
    (net (code "94") (name "unconnected-(U1-PC3{slash}SPI2_MOSI_{slash}I2S2_SD{slash}OTG_HS_ULPI_NXT{slash}ETH_MII_TX_CLK{slash}EVENTOUT{slash}ADC123_IN13-Pad18)") (class "Default")
      (node (ref "U1") (pin "18") (pinfunction "PC3/SPI2_MOSI_/I2S2_SD/OTG_HS_ULPI_NXT/ETH_MII_TX_CLK/EVENTOUT/ADC123_IN13_18") (pintype "bidirectional+no_connect"))
    )
    (net (code "95") (name "unconnected-(U1-PC6{slash}I2S2_MCK{slash}TIM8_CH1{slash}SDIO_D6{slash}USART6_TX{slash}DCMI_D0{slash}TIM3_CH1{slash}EVENTOUT-Pad63)") (class "Default")
      (node (ref "U1") (pin "63") (pinfunction "PC6/I2S2_MCK/TIM8_CH1/SDIO_D6/USART6_TX/DCMI_D0/TIM3_CH1/EVENTOUT_63") (pintype "bidirectional+no_connect"))
    )
    (net (code "96") (name "unconnected-(U1-PC7{slash}I2S3_MCK{slash}TIM8_CH2{slash}SDIO_D7{slash}USART6_RX{slash}DCMI_D1{slash}TIM3_CH2{slash}EVENTOUT-Pad64)") (class "Default")
      (node (ref "U1") (pin "64") (pinfunction "PC7/I2S3_MCK/TIM8_CH2/SDIO_D7/USART6_RX/DCMI_D1/TIM3_CH2/EVENTOUT_64") (pintype "bidirectional+no_connect"))
    )
    (net (code "97") (name "unconnected-(U1-PC15{slash}EVENTOUT{slash}OSC32_OUT-Pad9)") (class "Default")
      (node (ref "U1") (pin "9") (pinfunction "PC15/EVENTOUT/OSC32_OUT_9") (pintype "bidirectional+no_connect"))
    )
    (net (code "98") (name "unconnected-(U1-PD0{slash}FSMC_D2{slash}CAN1_RX{slash}EVENTOUT-Pad81)") (class "Default")
      (node (ref "U1") (pin "81") (pinfunction "PD0/FSMC_D2/CAN1_RX/EVENTOUT_81") (pintype "bidirectional+no_connect"))
    )
    (net (code "99") (name "unconnected-(U1-PD1{slash}FSMC_D3{slash}CAN1_TX{slash}EVENTOUT-Pad82)") (class "Default")
      (node (ref "U1") (pin "82") (pinfunction "PD1/FSMC_D3/CAN1_TX/EVENTOUT_82") (pintype "bidirectional+no_connect"))
    )
    (net (code "100") (name "unconnected-(U1-PD3{slash}FSMC_CLK{slash}USART2_CTS{slash}EVENTOUT-Pad84)") (class "Default")
      (node (ref "U1") (pin "84") (pinfunction "PD3/FSMC_CLK/USART2_CTS/EVENTOUT_84") (pintype "bidirectional+no_connect"))
    )
    (net (code "101") (name "unconnected-(U1-PD4{slash}FSMC_NOE{slash}USART2_RTS{slash}EVENTOUT-Pad85)") (class "Default")
      (node (ref "U1") (pin "85") (pinfunction "PD4/FSMC_NOE/USART2_RTS/EVENTOUT_85") (pintype "bidirectional+no_connect"))
    )
    (net (code "102") (name "unconnected-(U1-PD5{slash}FSMC_NWE{slash}USART2_TX{slash}EVENTOUT-Pad86)") (class "Default")
      (node (ref "U1") (pin "86") (pinfunction "PD5/FSMC_NWE/USART2_TX/EVENTOUT_86") (pintype "bidirectional+no_connect"))
    )
    (net (code "103") (name "unconnected-(U1-PD6{slash}FSMC_NWAIT{slash}USART2_RX{slash}EVENTOUT-Pad87)") (class "Default")
      (node (ref "U1") (pin "87") (pinfunction "PD6/FSMC_NWAIT/USART2_RX/EVENTOUT_87") (pintype "bidirectional+no_connect"))
    )
    (net (code "104") (name "unconnected-(U1-PD7{slash}USART2_CK{slash}FSMC_NE1{slash}FSMC_NCE2{slash}EVENTOUT-Pad88)") (class "Default")
      (node (ref "U1") (pin "88") (pinfunction "PD7/USART2_CK/FSMC_NE1/FSMC_NCE2/EVENTOUT_88") (pintype "bidirectional+no_connect"))
    )
    (net (code "105") (name "unconnected-(U1-PD8{slash}FSMC_D13{slash}USART3_TX{slash}EVENTOUT-Pad55)") (class "Default")
      (node (ref "U1") (pin "55") (pinfunction "PD8/FSMC_D13/USART3_TX/EVENTOUT_55") (pintype "bidirectional+no_connect"))
    )
    (net (code "106") (name "unconnected-(U1-PD9{slash}FSMC_D14{slash}USART3_RX{slash}EVENTOUT-Pad56)") (class "Default")
      (node (ref "U1") (pin "56") (pinfunction "PD9/FSMC_D14/USART3_RX/EVENTOUT_56") (pintype "bidirectional+no_connect"))
    )
    (net (code "107") (name "unconnected-(U1-PD10{slash}FSMC_D15{slash}USART3_CK{slash}EVENTOUT-Pad57)") (class "Default")
      (node (ref "U1") (pin "57") (pinfunction "PD10/FSMC_D15/USART3_CK/EVENTOUT_57") (pintype "bidirectional+no_connect"))
    )
    (net (code "108") (name "unconnected-(U1-PD11{slash}FSMC_CLE{slash}FSMC_A16{slash}USART3_CTS{slash}EVENTOUT-Pad58)") (class "Default")
      (node (ref "U1") (pin "58") (pinfunction "PD11/FSMC_CLE/FSMC_A16/USART3_CTS/EVENTOUT_58") (pintype "bidirectional+no_connect"))
    )
    (net (code "109") (name "unconnected-(U1-PD13{slash}FSMC_A18{slash}TIM4_CH2{slash}EVENTOUT-Pad60)") (class "Default")
      (node (ref "U1") (pin "60") (pinfunction "PD13/FSMC_A18/TIM4_CH2/EVENTOUT_60") (pintype "bidirectional+no_connect"))
    )
    (net (code "110") (name "unconnected-(U1-PD14{slash}FSMC_D0{slash}TIM4_CH3{slash}EVENTOUT{slash}EVENTOUT-Pad61)") (class "Default")
      (node (ref "U1") (pin "61") (pinfunction "PD14/FSMC_D0/TIM4_CH3/EVENTOUT/EVENTOUT_61") (pintype "bidirectional+no_connect"))
    )
    (net (code "111") (name "unconnected-(U1-PD15{slash}FSMC_D1{slash}TIM4_CH4{slash}EVENTOUT-Pad62)") (class "Default")
      (node (ref "U1") (pin "62") (pinfunction "PD15/FSMC_D1/TIM4_CH4/EVENTOUT_62") (pintype "bidirectional+no_connect"))
    )
    (net (code "112") (name "unconnected-(U1-PE0{slash}TIM4_ETR{slash}FSMC_NBL0{slash}DCMI_D2{slash}EVENTOUT-Pad97)") (class "Default")
      (node (ref "U1") (pin "97") (pinfunction "PE0/TIM4_ETR/FSMC_NBL0/DCMI_D2/EVENTOUT_97") (pintype "bidirectional+no_connect"))
    )
    (net (code "113") (name "unconnected-(U1-PE1{slash}FSMC_NBL1{slash}DCMI_D3{slash}EVENTOUT-Pad98)") (class "Default")
      (node (ref "U1") (pin "98") (pinfunction "PE1/FSMC_NBL1/DCMI_D3/EVENTOUT_98") (pintype "bidirectional+no_connect"))
    )
    (net (code "114") (name "unconnected-(U1-PE4{slash}TRACED1{slash}FSMC_A20{slash}DCMI_D4{slash}EVENTOUT-Pad3)") (class "Default")
      (node (ref "U1") (pin "3") (pinfunction "PE4/TRACED1/FSMC_A20/DCMI_D4/EVENTOUT_3") (pintype "bidirectional+no_connect"))
    )
    (net (code "115") (name "unconnected-(U1-PE6{slash}TRACED3_{slash}_FSMC_A22{slash}TIM9_CH2{slash}DCMI_D7{slash}EVENTOUT-Pad5)") (class "Default")
      (node (ref "U1") (pin "5") (pinfunction "PE6/TRACED3_/_FSMC_A22/TIM9_CH2/DCMI_D7/EVENTOUT_5") (pintype "bidirectional+no_connect"))
    )
    (net (code "116") (name "unconnected-(U1-PE7{slash}FSMC_D4{slash}TIM1_ETR{slash}EVENTOUT-Pad38)") (class "Default")
      (node (ref "U1") (pin "38") (pinfunction "PE7/FSMC_D4/TIM1_ETR/EVENTOUT_38") (pintype "bidirectional+no_connect"))
    )
    (net (code "117") (name "unconnected-(U1-PE8{slash}FSMC_D5{slash}TIM1_CH1N{slash}EVENTOUT-Pad39)") (class "Default")
      (node (ref "U1") (pin "39") (pinfunction "PE8/FSMC_D5/TIM1_CH1N/EVENTOUT_39") (pintype "bidirectional+no_connect"))
    )
    (net (code "118") (name "unconnected-(U1-PE9{slash}FSMC_D6{slash}TIM1_CH1{slash}EVENTOUT-Pad40)") (class "Default")
      (node (ref "U1") (pin "40") (pinfunction "PE9/FSMC_D6/TIM1_CH1/EVENTOUT_40") (pintype "bidirectional+no_connect"))
    )
    (net (code "119") (name "unconnected-(U1-PE10{slash}FSMC_D7{slash}TIM1_CH2N{slash}EVENTOUT-Pad41)") (class "Default")
      (node (ref "U1") (pin "41") (pinfunction "PE10/FSMC_D7/TIM1_CH2N/EVENTOUT_41") (pintype "bidirectional+no_connect"))
    )
    (net (code "120") (name "unconnected-(U1-PE11{slash}FSMC_D8{slash}TIM1_CH2{slash}EVENTOUT-Pad42)") (class "Default")
      (node (ref "U1") (pin "42") (pinfunction "PE11/FSMC_D8/TIM1_CH2/EVENTOUT_42") (pintype "bidirectional+no_connect"))
    )
    (net (code "121") (name "unconnected-(U1-PE12{slash}FSMC_D9{slash}TIM1_CH3N{slash}EVENTOUT-Pad43)") (class "Default")
      (node (ref "U1") (pin "43") (pinfunction "PE12/FSMC_D9/TIM1_CH3N/EVENTOUT_43") (pintype "bidirectional+no_connect"))
    )
    (net (code "122") (name "unconnected-(U1-PE13{slash}FSMC_D10{slash}TIM1_CH3{slash}EVENTOUT-Pad44)") (class "Default")
      (node (ref "U1") (pin "44") (pinfunction "PE13/FSMC_D10/TIM1_CH3/EVENTOUT_44") (pintype "bidirectional+no_connect"))
    )
    (net (code "123") (name "unconnected-(U1-PE14{slash}FSMC_D11{slash}TIM1_CH4{slash}EVENTOUT-Pad45)") (class "Default")
      (node (ref "U1") (pin "45") (pinfunction "PE14/FSMC_D11/TIM1_CH4/EVENTOUT_45") (pintype "bidirectional+no_connect"))
    )
    (net (code "124") (name "unconnected-(U1-PE15{slash}FSMC_D12{slash}TIM1_BKIN{slash}EVENTOUT-Pad46)") (class "Default")
      (node (ref "U1") (pin "46") (pinfunction "PE15/FSMC_D12/TIM1_BKIN/EVENTOUT_46") (pintype "bidirectional+no_connect"))
    )
    (net (code "125") (name "unconnected-(U2-AUX_CL-Pad7)") (class "Default")
      (node (ref "U2") (pin "7") (pinfunction "AUX_CL_7") (pintype "input+no_connect"))
    )
    (net (code "126") (name "unconnected-(U2-AUX_DA-Pad21)") (class "Default")
      (node (ref "U2") (pin "21") (pinfunction "AUX_DA_21") (pintype "bidirectional+no_connect"))
    )
    (net (code "127") (name "unconnected-(U2-NC-Pad2)") (class "Default")
      (node (ref "U2") (pin "2") (pinfunction "NC_2") (pintype "passive+no_connect"))
    )
    (net (code "128") (name "unconnected-(U2-NC-Pad3)") (class "Default")
      (node (ref "U2") (pin "3") (pinfunction "NC_3") (pintype "passive+no_connect"))
    )
    (net (code "129") (name "unconnected-(U2-NC-Pad4)") (class "Default")
      (node (ref "U2") (pin "4") (pinfunction "NC_4") (pintype "passive+no_connect"))
    )
    (net (code "130") (name "unconnected-(U2-NC-Pad5)") (class "Default")
      (node (ref "U2") (pin "5") (pinfunction "NC_5") (pintype "passive+no_connect"))
    )
    (net (code "131") (name "unconnected-(U2-NC-Pad6)") (class "Default")
      (node (ref "U2") (pin "6") (pinfunction "NC_6") (pintype "passive+no_connect"))
    )
    (net (code "132") (name "unconnected-(U2-NC-Pad14)") (class "Default")
      (node (ref "U2") (pin "14") (pinfunction "NC_14") (pintype "passive+no_connect"))
    )
    (net (code "133") (name "unconnected-(U2-NC-Pad15)") (class "Default")
      (node (ref "U2") (pin "15") (pinfunction "NC_15") (pintype "passive+no_connect"))
    )
    (net (code "134") (name "unconnected-(U2-NC-Pad16)") (class "Default")
      (node (ref "U2") (pin "16") (pinfunction "NC_16") (pintype "passive+no_connect"))
    )
    (net (code "135") (name "unconnected-(U2-NC-Pad17)") (class "Default")
      (node (ref "U2") (pin "17") (pinfunction "NC_17") (pintype "passive+no_connect"))
    )
    (net (code "136") (name "unconnected-(U2-RESV-Pad19)") (class "Default")
      (node (ref "U2") (pin "19") (pinfunction "RESV_19") (pintype "passive+no_connect"))
    )
    (net (code "137") (name "unconnected-(U5-CSB-Pad1)") (class "Default")
      (node (ref "U5") (pin "1") (pinfunction "CSB_1") (pintype "passive+no_connect"))
    )
    (net (code "138") (name "unconnected-(U5-SDO-Pad4)") (class "Default")
      (node (ref "U5") (pin "4") (pinfunction "SDO_4") (pintype "passive+no_connect"))
    )
    (net (code "139") (name "unconnected-(U6-NC-Pad6)") (class "Default")
      (node (ref "U6") (pin "6") (pinfunction "NC_6") (pintype "power_in+no_connect"))
    )
  )
)
